# power.net
KiCad netlist of a schematic drawn in Altium Designer
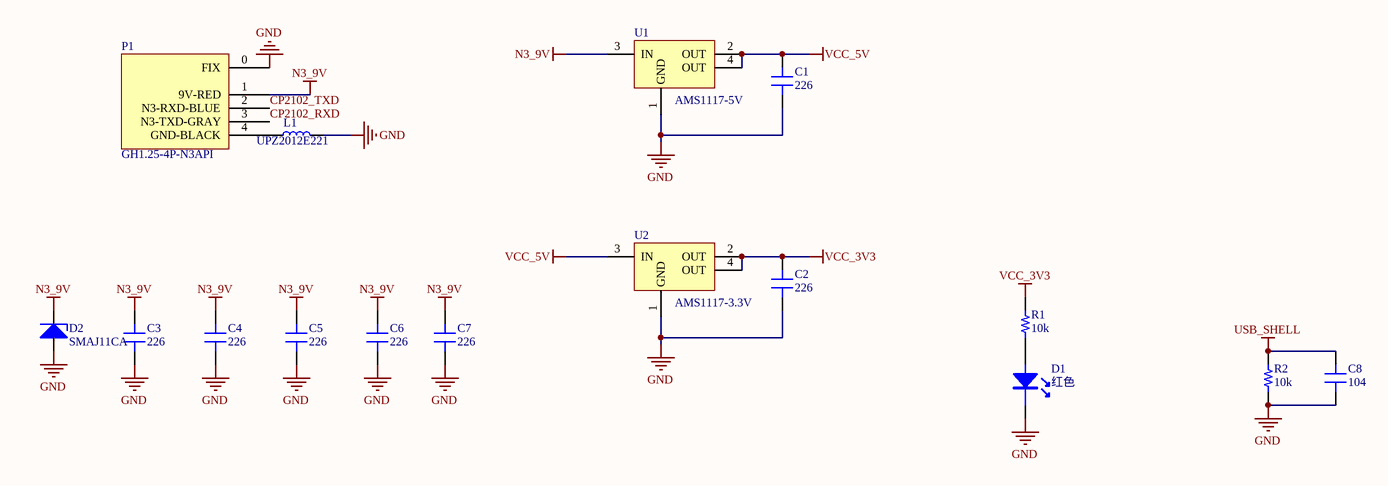
[diagram p0: power.SchDoc]

(export (version "E")
  (design (tool "Eeschema 10.0.6"))
  (components
    (comp (ref "C1")
      (value "226")
      (footprint "C0603/1608")
      (description "陶瓷电容")
      (libsource (lib "WMJ2019_Devices") (part "陶瓷电容"))
    )
    (comp (ref "C2")
      (value "226")
      (footprint "C0603/1608")
      (description "陶瓷电容")
      (libsource (lib "WMJ2019_Devices") (part "陶瓷电容"))
    )
    (comp (ref "C3")
      (value "226")
      (footprint "C1206/3216")
      (description "陶瓷电容")
      (libsource (lib "WMJ2019_Devices") (part "陶瓷电容"))
    )
    (comp (ref "C4")
      (value "226")
      (footprint "C1206/3216")
      (description "陶瓷电容")
      (libsource (lib "WMJ2019_Devices") (part "陶瓷电容"))
    )
    (comp (ref "C5")
      (value "226")
      (footprint "C1206/3216")
      (description "陶瓷电容")
      (libsource (lib "WMJ2019_Devices") (part "陶瓷电容"))
    )
    (comp (ref "C6")
      (value "226")
      (footprint "C1206/3216")
      (description "陶瓷电容")
      (libsource (lib "WMJ2019_Devices") (part "陶瓷电容"))
    )
    (comp (ref "C7")
      (value "226")
      (footprint "C1206/3216")
      (description "陶瓷电容")
      (libsource (lib "WMJ2019_Devices") (part "陶瓷电容"))
    )
    (comp (ref "C8")
      (value "104")
      (footprint "C0603/1608")
      (description "陶瓷电容")
      (libsource (lib "WMJ2019_Devices") (part "陶瓷电容"))
    )
    (comp (ref "D1")
      (value "LED-红色")
      (footprint "LED0603-蓝色")
      (description "发光二极管")
      (fields (field (name "COLOR") "红色"))
      (libsource (lib "Devices") (part "LED"))
    )
    (comp (ref "D2")
      (value "SMAJ11CA")
      (footprint "DO-214AC/SMA")
      (description "瞬态抑制二极管")
      (libsource (lib "Devices") (part "瞬态抑制二极管"))
    )
    (comp (ref "L1")
      (value "UPZ2012E221")
      (footprint "L0805/2012")
      (description "贴片磁珠")
      (libsource (lib "WMJ2019_Devices") (part "磁珠"))
    )
    (comp (ref "P1")
      (value "GH1.25-4P-N3API")
      (footprint "GH1.25-4P（卧贴）")
      (libsource (lib "Connectors") (part "GH1.25-4P-N3API"))
    )
    (comp (ref "R1")
      (value "10k")
      (footprint "R0603/1608")
      (description "电阻")
      (libsource (lib "WMJ2019_Devices") (part "电阻"))
    )
    (comp (ref "R2")
      (value "10k")
      (footprint "R0603/1608")
      (description "电阻")
      (libsource (lib "WMJ2019_Devices") (part "电阻"))
    )
    (comp (ref "U1")
      (value "AMS1117-5V")
      (footprint "SOT-223")
      (description "AMS1117低压差线性稳压器")
      (libsource (lib "WMJ2019_Devices") (part "AMS1117"))
    )
    (comp (ref "U2")
      (value "AMS1117-3.3V")
      (footprint "SOT-223")
      (description "AMS1117低压差线性稳压器")
      (libsource (lib "WMJ2019_Devices") (part "AMS1117"))
    )
  )
  (nets
    (net (code "1") (name "/CP2102_RXD") (class "Default")
      (node (ref "P1") (pin "3") (pinfunction "N3-TXD-GRAY_3") (pintype "passive"))
    )
    (net (code "2") (name "/CP2102_TXD") (class "Default")
      (node (ref "P1") (pin "2") (pinfunction "N3-RXD-BLUE_2") (pintype "passive"))
    )
    (net (code "3") (name "GND") (class "Default")
      (node (ref "C1") (pin "1") (pintype "passive"))
      (node (ref "C2") (pin "1") (pintype "passive"))
      (node (ref "C3") (pin "1") (pintype "passive"))
      (node (ref "C4") (pin "1") (pintype "passive"))
      (node (ref "C5") (pin "1") (pintype "passive"))
      (node (ref "C6") (pin "1") (pintype "passive"))
      (node (ref "C7") (pin "1") (pintype "passive"))
      (node (ref "C8") (pin "1") (pintype "passive"))
      (node (ref "D1") (pin "2") (pinfunction "K_2") (pintype "passive"))
      (node (ref "D2") (pin "1") (pinfunction "+_1") (pintype "passive"))
      (node (ref "L1") (pin "1") (pinfunction "1_1") (pintype "passive"))
      (node (ref "P1") (pin "0") (pinfunction "FIX_0") (pintype "passive"))
      (node (ref "R2") (pin "1") (pintype "passive"))
      (node (ref "U1") (pin "1") (pinfunction "GND_1") (pintype "passive"))
      (node (ref "U2") (pin "1") (pinfunction "GND_1") (pintype "passive"))
    )
    (net (code "4") (name "N3_9V") (class "Default")
      (node (ref "C3") (pin "2") (pintype "passive"))
      (node (ref "C4") (pin "2") (pintype "passive"))
      (node (ref "C5") (pin "2") (pintype "passive"))
      (node (ref "C6") (pin "2") (pintype "passive"))
      (node (ref "C7") (pin "2") (pintype "passive"))
      (node (ref "D2") (pin "2") (pinfunction "-_2") (pintype "passive"))
      (node (ref "P1") (pin "1") (pinfunction "9V-RED_1") (pintype "passive"))
      (node (ref "U1") (pin "3") (pinfunction "IN_3") (pintype "passive"))
    )
    (net (code "5") (name "Net-(D1-A)") (class "Default")
      (node (ref "D1") (pin "1") (pinfunction "A_1") (pintype "passive"))
      (node (ref "R1") (pin "1") (pintype "passive"))
    )
    (net (code "6") (name "Net-(P1-GND-BLACK)") (class "Default")
      (node (ref "L1") (pin "2") (pinfunction "2_2") (pintype "passive"))
      (node (ref "P1") (pin "4") (pinfunction "GND-BLACK_4") (pintype "passive"))
    )
    (net (code "7") (name "USB_SHELL") (class "Default")
      (node (ref "C8") (pin "2") (pintype "passive"))
      (node (ref "R2") (pin "2") (pintype "passive"))
    )
    (net (code "8") (name "VCC_3V3") (class "Default")
      (node (ref "C2") (pin "2") (pintype "passive"))
      (node (ref "R1") (pin "2") (pintype "passive"))
      (node (ref "U2") (pin "2") (pinfunction "OUT_2") (pintype "passive"))
      (node (ref "U2") (pin "4") (pinfunction "OUT_4") (pintype "passive"))
    )
    (net (code "9") (name "VCC_5V") (class "Default")
      (node (ref "C1") (pin "2") (pintype "passive"))
      (node (ref "U1") (pin "2") (pinfunction "OUT_2") (pintype "passive"))
      (node (ref "U1") (pin "4") (pinfunction "OUT_4") (pintype "passive"))
      (node (ref "U2") (pin "3") (pinfunction "IN_3") (pintype "passive"))
    )
  )
)
